# Battery_Management.net
KiCad netlist of a schematic drawn in Altium Designer
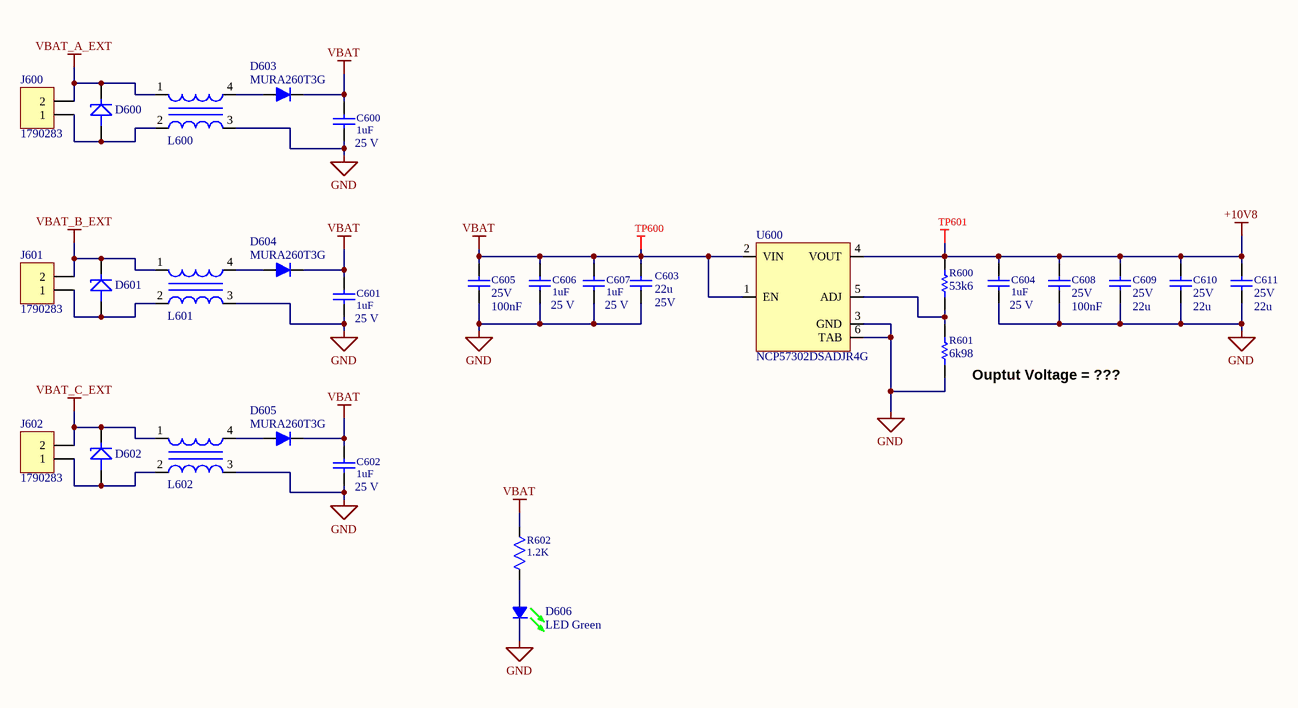
[diagram p0: Battery Management.SchDoc]

(export (version "E")
  (design (tool "Eeschema 10.0.6"))
  (components
    (comp (ref "C600")
      (value "1uF")
      (footprint "C1608[0603] small")
      (description "CAP 1µF 25V ±10% X7R 0603")
      (fields
        (field (name "MANUFACTURER") "Samsung")
        (field (name "MANUFACTURER PART NUMBER") "CL10B105KA8NNNC")
        (field (name "VOLTAGE") "25 V")
      )
      (libsource (lib "Capacitors") (part "1uF_0603_25V"))
    )
    (comp (ref "C601")
      (value "1uF")
      (footprint "C1608[0603] small")
      (description "CAP 1µF 25V ±10% X7R 0603")
      (fields
        (field (name "MANUFACTURER") "Samsung")
        (field (name "MANUFACTURER PART NUMBER") "CL10B105KA8NNNC")
        (field (name "VOLTAGE") "25 V")
      )
      (libsource (lib "Capacitors") (part "1uF_0603_25V"))
    )
    (comp (ref "C602")
      (value "1uF")
      (footprint "C1608[0603] small")
      (description "CAP 1µF 25V ±10% X7R 0603")
      (fields
        (field (name "MANUFACTURER") "Samsung")
        (field (name "MANUFACTURER PART NUMBER") "CL10B105KA8NNNC")
        (field (name "VOLTAGE") "25 V")
      )
      (libsource (lib "Capacitors") (part "1uF_0603_25V"))
    )
    (comp (ref "C603")
      (value "22u")
      (footprint "CAPC2012X14N")
      (fields
        (field (name "VOLTAGE") "25V")
        (field (name "MANUFACTURER PART NUMBER") "GRM21BR61E226ME44K")
        (field (name "MANUFACTURER") "Murata")
      )
      (libsource (lib "Capacitors") (part "4.7uF_0603_10V"))
    )
    (comp (ref "C604")
      (value "1uF")
      (footprint "C1608[0603] small")
      (description "CAP 1µF 25V ±10% X7R 0603")
      (fields
        (field (name "MANUFACTURER") "Samsung")
        (field (name "MANUFACTURER PART NUMBER") "CL10B105KA8NNNC")
        (field (name "VOLTAGE") "25 V")
      )
      (libsource (lib "Capacitors") (part "1uF_0603_25V"))
    )
    (comp (ref "C605")
      (value "100nF")
      (footprint "CAPC1005X06N")
      (fields
        (field (name "VOLTAGE") "25V")
        (field (name "MANUFACTURER PART NUMBER") "CL05A104KA5NNNC")
        (field (name "MANUFACTURER") "Samsung")
        (field (name "Comment") "4.7uF")
      )
      (libsource (lib "Capacitors") (part "4.7uF_0603_10V"))
    )
    (comp (ref "C606")
      (value "1uF")
      (footprint "C1608[0603] small")
      (description "CAP 1µF 25V ±10% X7R 0603")
      (fields
        (field (name "MANUFACTURER") "Samsung")
        (field (name "MANUFACTURER PART NUMBER") "CL10B105KA8NNNC")
        (field (name "VOLTAGE") "25 V")
      )
      (libsource (lib "Capacitors") (part "1uF_0603_25V"))
    )
    (comp (ref "C607")
      (value "1uF")
      (footprint "C1608[0603] small")
      (description "CAP 1µF 25V ±10% X7R 0603")
      (fields
        (field (name "MANUFACTURER") "Samsung")
        (field (name "MANUFACTURER PART NUMBER") "CL10B105KA8NNNC")
        (field (name "VOLTAGE") "25 V")
      )
      (libsource (lib "Capacitors") (part "1uF_0603_25V"))
    )
    (comp (ref "C608")
      (value "100nF")
      (footprint "CAPC1005X06N")
      (fields
        (field (name "VOLTAGE") "25V")
        (field (name "MANUFACTURER PART NUMBER") "CL05A104KA5NNNC")
        (field (name "MANUFACTURER") "Samsung")
        (field (name "Comment") "4.7uF")
      )
      (libsource (lib "Capacitors") (part "4.7uF_0603_10V"))
    )
    (comp (ref "C609")
      (value "22u")
      (footprint "CAPC2012X14N")
      (fields
        (field (name "VOLTAGE") "25V")
        (field (name "MANUFACTURER PART NUMBER") "GRM21BR61E226ME44K")
        (field (name "MANUFACTURER") "Murata")
      )
      (libsource (lib "Capacitors") (part "4.7uF_0603_10V"))
    )
    (comp (ref "C610")
      (value "22u")
      (footprint "CAPC2012X14N")
      (fields
        (field (name "VOLTAGE") "25V")
        (field (name "MANUFACTURER PART NUMBER") "GRM21BR61E226ME44K")
        (field (name "MANUFACTURER") "Murata")
      )
      (libsource (lib "Capacitors") (part "4.7uF_0603_10V"))
    )
    (comp (ref "C611")
      (value "22u")
      (footprint "CAPC2012X14N")
      (fields
        (field (name "VOLTAGE") "25V")
        (field (name "MANUFACTURER PART NUMBER") "GRM21BR61E226ME44K")
        (field (name "MANUFACTURER") "Murata")
      )
      (libsource (lib "Capacitors") (part "4.7uF_0603_10V"))
    )
    (comp (ref "D600")
      (value "12V TVS")
      (footprint "NXP PTVSxS1UR-Series (SOD123W)")
      (fields
        (field (name "MANUFACTURER") "Nexperia")
        (field (name "MANUFACTURER PART NUMBER") "PTVS12VS1UR,115")
      )
      (libsource (lib "FSM_2018") (part "NXP PTVSxS1UR-Series"))
    )
    (comp (ref "D601")
      (value "12V TVS")
      (footprint "NXP PTVSxS1UR-Series (SOD123W)")
      (fields
        (field (name "MANUFACTURER") "Nexperia")
        (field (name "MANUFACTURER PART NUMBER") "PTVS12VS1UR,115")
      )
      (libsource (lib "FSM_2018") (part "NXP PTVSxS1UR-Series"))
    )
    (comp (ref "D602")
      (value "12V TVS")
      (footprint "NXP PTVSxS1UR-Series (SOD123W)")
      (fields
        (field (name "MANUFACTURER") "Nexperia")
        (field (name "MANUFACTURER PART NUMBER") "PTVS12VS1UR,115")
      )
      (libsource (lib "FSM_2018") (part "NXP PTVSxS1UR-Series"))
    )
    (comp (ref "D603")
      (value "MURA260T3G")
      (footprint "Diode SMA DIOM5226X240N")
      (description "Diode Standard 600V 2A Surface Mount SMA")
      (fields (field (name "MANUFACTURER") "ON Semi") (field (name "MANUFACTURER PART NUMBER") "MURA260T3G"))
      (libsource (lib "Gas Monitor Components") (part "MURA260T3G"))
    )
    (comp (ref "D604")
      (value "MURA260T3G")
      (footprint "Diode SMA DIOM5226X240N")
      (description "Diode Standard 600V 2A Surface Mount SMA")
      (fields (field (name "MANUFACTURER") "ON Semi") (field (name "MANUFACTURER PART NUMBER") "MURA260T3G"))
      (libsource (lib "Gas Monitor Components") (part "MURA260T3G"))
    )
    (comp (ref "D605")
      (value "MURA260T3G")
      (footprint "Diode SMA DIOM5226X240N")
      (description "Diode Standard 600V 2A Surface Mount SMA")
      (fields (field (name "MANUFACTURER") "ON Semi") (field (name "MANUFACTURER PART NUMBER") "MURA260T3G"))
      (libsource (lib "Gas Monitor Components") (part "MURA260T3G"))
    )
    (comp (ref "D606")
      (value "LED Green")
      (footprint "LED_0603")
      (description "LED Green Diffused 0603")
      (fields (field (name "MANUFACTURER") "Rohm") (field (name "MANUFACTURER PART NUMBER") "SML-D12M8WT86"))
      (libsource (lib "LEDs") (part "Green LED"))
    )
    (comp (ref "J600")
      (value "1790283")
      (footprint "5.08mm 2pos TermBlock")
      (description "5.08mm Spring Cage, Tension Clamp, Pheonix Contact, 2pos, THD")
      (fields (field (name "MANUFACTURER") "Phoenix Contact"))
      (libsource (lib "Connectors-V") (part "TERM BLOCK 2POS 45DEG 5.08MM"))
    )
    (comp (ref "J601")
      (value "1790283")
      (footprint "5.08mm 2pos TermBlock")
      (description "5.08mm Spring Cage, Tension Clamp, Pheonix Contact, 2pos, THD")
      (fields (field (name "MANUFACTURER") "Phoenix Contact"))
      (libsource (lib "Connectors-V") (part "TERM BLOCK 2POS 45DEG 5.08MM"))
    )
    (comp (ref "J602")
      (value "1790283")
      (footprint "5.08mm 2pos TermBlock")
      (description "5.08mm Spring Cage, Tension Clamp, Pheonix Contact, 2pos, THD")
      (fields (field (name "MANUFACTURER") "Phoenix Contact"))
      (libsource (lib "Connectors-V") (part "TERM BLOCK 2POS 45DEG 5.08MM"))
    )
    (comp (ref "L600")
      (value "CM3421Y600R-10")
      (footprint "CM3421Y600R-10")
      (description "2 Line Common Mode Choke Surface Mount 60 Ohms @ 100MHz 15A DCR 0.75mOhm")
      (fields (field (name "MANUFACTURER") "Laird"))
      (libsource (lib "Gas Monitor Components") (part "CM3421Y600R-10"))
    )
    (comp (ref "L601")
      (value "CM3421Y600R-10")
      (footprint "CM3421Y600R-10")
      (description "2 Line Common Mode Choke Surface Mount 60 Ohms @ 100MHz 15A DCR 0.75mOhm")
      (fields (field (name "MANUFACTURER") "Laird"))
      (libsource (lib "Gas Monitor Components") (part "CM3421Y600R-10"))
    )
    (comp (ref "L602")
      (value "CM3421Y600R-10")
      (footprint "CM3421Y600R-10")
      (description "2 Line Common Mode Choke Surface Mount 60 Ohms @ 100MHz 15A DCR 0.75mOhm")
      (fields (field (name "MANUFACTURER") "Laird"))
      (libsource (lib "Gas Monitor Components") (part "CM3421Y600R-10"))
    )
    (comp (ref "R600")
      (value "53k6")
      (footprint "RESC1608X06N")
      (fields
        (field (name "MANUFACTURER") "Panasonic")
        (field (name "MANUFACTURER PART NUMBER") "ERA-3AEB5362V")
        (field (name "Comment") "RES: GENERAL")
      )
      (libsource (lib "Santuary") (part "RES{colon} GENERAL"))
    )
    (comp (ref "R601")
      (value "6k98")
      (footprint "RESC1608X06N")
      (fields
        (field (name "MANUFACTURER") "Panasonic")
        (field (name "MANUFACTURER PART NUMBER") "ERA-3AEB6981V")
        (field (name "Comment") "RES: GENERAL")
      )
      (libsource (lib "Santuary") (part "RES{colon} GENERAL"))
    )
    (comp (ref "R602")
      (value "1.2K")
      (footprint "R1608[0603] small")
      (description "RES 1K Ohm ±5%, 0.25W,1/4W 0603")
      (fields
        (field (name "MANUFACTURER") "Yageo")
        (field (name "MANUFACTURER PART NUMBER") "RC0603FR-071K2L")
      )
      (libsource (lib "Resistors") (part "1K00_0603_0.1W"))
    )
    (comp (ref "TP600")
      (value "PAD")
      (footprint "TP_SMD_39MIL")
      (description "SMD Test Pad")
      (fields (field (name "MANUFACTURER") "No P/N Required"))
      (libsource (lib "Connectors") (part "TP_SMD_39MIL"))
    )
    (comp (ref "TP601")
      (value "PAD")
      (footprint "TP_SMD_39MIL")
      (description "SMD Test Pad")
      (fields (field (name "MANUFACTURER") "No P/N Required"))
      (libsource (lib "Connectors") (part "TP_SMD_39MIL"))
    )
    (comp (ref "U600")
      (value "NCP57302DSADJR4G")
      (footprint "D2PAK-5")
      (description "Linear Voltage Regulator IC Positive Adjustable 1 Output  3A D2PAK-5")
      (fields (field (name "MANUFACTURER") "ON Semiconductor"))
      (libsource (lib "Gas Monitor Components") (part "NCP57302DSADJR4G"))
    )
  )
  (nets
    (net (code "1") (name "+10V8") (class "Default")
      (node (ref "C604") (pin "2") (pintype "passive"))
      (node (ref "C608") (pin "1") (pintype "passive"))
      (node (ref "C609") (pin "1") (pintype "passive"))
      (node (ref "C610") (pin "1") (pintype "passive"))
      (node (ref "C611") (pin "1") (pintype "passive"))
      (node (ref "R600") (pin "1") (pinfunction "1_1") (pintype "passive"))
      (node (ref "TP601") (pin "1") (pintype "passive"))
      (node (ref "U600") (pin "4") (pinfunction "VOUT_4") (pintype "passive"))
    )
    (net (code "2") (name "GND") (class "Default")
      (node (ref "C600") (pin "1") (pintype "passive"))
      (node (ref "C601") (pin "1") (pintype "passive"))
      (node (ref "C602") (pin "1") (pintype "passive"))
      (node (ref "C603") (pin "2") (pintype "passive"))
      (node (ref "C604") (pin "1") (pintype "passive"))
      (node (ref "C605") (pin "2") (pintype "passive"))
      (node (ref "C606") (pin "1") (pintype "passive"))
      (node (ref "C607") (pin "1") (pintype "passive"))
      (node (ref "C608") (pin "2") (pintype "passive"))
      (node (ref "C609") (pin "2") (pintype "passive"))
      (node (ref "C610") (pin "2") (pintype "passive"))
      (node (ref "C611") (pin "2") (pintype "passive"))
      (node (ref "D606") (pin "2") (pintype "passive"))
      (node (ref "L600") (pin "3") (pinfunction "3_3") (pintype "passive"))
      (node (ref "L601") (pin "3") (pinfunction "3_3") (pintype "passive"))
      (node (ref "L602") (pin "3") (pinfunction "3_3") (pintype "passive"))
      (node (ref "R601") (pin "2") (pinfunction "2_2") (pintype "passive"))
      (node (ref "U600") (pin "3") (pinfunction "GND_3") (pintype "passive"))
      (node (ref "U600") (pin "6") (pinfunction "TAB_6") (pintype "passive"))
    )
    (net (code "3") (name "Net-(D600-Pad2)") (class "Default")
      (node (ref "D600") (pin "2") (pinfunction "2_2") (pintype "passive"))
      (node (ref "J600") (pin "1") (pinfunction "1_1") (pintype "passive"))
      (node (ref "L600") (pin "2") (pinfunction "2_2") (pintype "passive"))
    )
    (net (code "4") (name "Net-(D601-Pad2)") (class "Default")
      (node (ref "D601") (pin "2") (pinfunction "2_2") (pintype "passive"))
      (node (ref "J601") (pin "1") (pinfunction "1_1") (pintype "passive"))
      (node (ref "L601") (pin "2") (pinfunction "2_2") (pintype "passive"))
    )
    (net (code "5") (name "Net-(D602-Pad2)") (class "Default")
      (node (ref "D602") (pin "2") (pinfunction "2_2") (pintype "passive"))
      (node (ref "J602") (pin "1") (pinfunction "1_1") (pintype "passive"))
      (node (ref "L602") (pin "2") (pinfunction "2_2") (pintype "passive"))
    )
    (net (code "6") (name "Net-(D603-A)") (class "Default")
      (node (ref "D603") (pin "2") (pinfunction "A_2") (pintype "passive"))
      (node (ref "L600") (pin "4") (pinfunction "4_4") (pintype "passive"))
    )
    (net (code "7") (name "Net-(D604-A)") (class "Default")
      (node (ref "D604") (pin "2") (pinfunction "A_2") (pintype "passive"))
      (node (ref "L601") (pin "4") (pinfunction "4_4") (pintype "passive"))
    )
    (net (code "8") (name "Net-(D605-A)") (class "Default")
      (node (ref "D605") (pin "2") (pinfunction "A_2") (pintype "passive"))
      (node (ref "L602") (pin "4") (pinfunction "4_4") (pintype "passive"))
    )
    (net (code "9") (name "Net-(D606-Pad1)") (class "Default")
      (node (ref "D606") (pin "1") (pintype "passive"))
      (node (ref "R602") (pin "1") (pintype "passive"))
    )
    (net (code "10") (name "Net-(U600-ADJ)") (class "Default")
      (node (ref "R600") (pin "2") (pinfunction "2_2") (pintype "passive"))
      (node (ref "R601") (pin "1") (pinfunction "1_1") (pintype "passive"))
      (node (ref "U600") (pin "5") (pinfunction "ADJ_5") (pintype "passive"))
    )
    (net (code "11") (name "VBAT") (class "Default")
      (node (ref "C600") (pin "2") (pintype "passive"))
      (node (ref "C601") (pin "2") (pintype "passive"))
      (node (ref "C602") (pin "2") (pintype "passive"))
      (node (ref "C603") (pin "1") (pintype "passive"))
      (node (ref "C605") (pin "1") (pintype "passive"))
      (node (ref "C606") (pin "2") (pintype "passive"))
      (node (ref "C607") (pin "2") (pintype "passive"))
      (node (ref "D603") (pin "1") (pinfunction "K_1") (pintype "passive"))
      (node (ref "D604") (pin "1") (pinfunction "K_1") (pintype "passive"))
      (node (ref "D605") (pin "1") (pinfunction "K_1") (pintype "passive"))
      (node (ref "R602") (pin "2") (pintype "passive"))
      (node (ref "TP600") (pin "1") (pintype "passive"))
      (node (ref "U600") (pin "1") (pinfunction "EN_1") (pintype "passive"))
      (node (ref "U600") (pin "2") (pinfunction "VIN_2") (pintype "passive"))
    )
    (net (code "12") (name "VBAT_A_EXT") (class "Default")
      (node (ref "D600") (pin "1") (pinfunction "1_1") (pintype "passive"))
      (node (ref "J600") (pin "2") (pinfunction "2_2") (pintype "passive"))
      (node (ref "L600") (pin "1") (pinfunction "1_1") (pintype "passive"))
    )
    (net (code "13") (name "VBAT_B_EXT") (class "Default")
      (node (ref "D601") (pin "1") (pinfunction "1_1") (pintype "passive"))
      (node (ref "J601") (pin "2") (pinfunction "2_2") (pintype "passive"))
      (node (ref "L601") (pin "1") (pinfunction "1_1") (pintype "passive"))
    )
    (net (code "14") (name "VBAT_C_EXT") (class "Default")
      (node (ref "D602") (pin "1") (pinfunction "1_1") (pintype "passive"))
      (node (ref "J602") (pin "2") (pinfunction "2_2") (pintype "passive"))
      (node (ref "L602") (pin "1") (pinfunction "1_1") (pintype "passive"))
    )
  )
)
